# Sheet1.net
KiCad netlist of a schematic drawn in Altium Designer
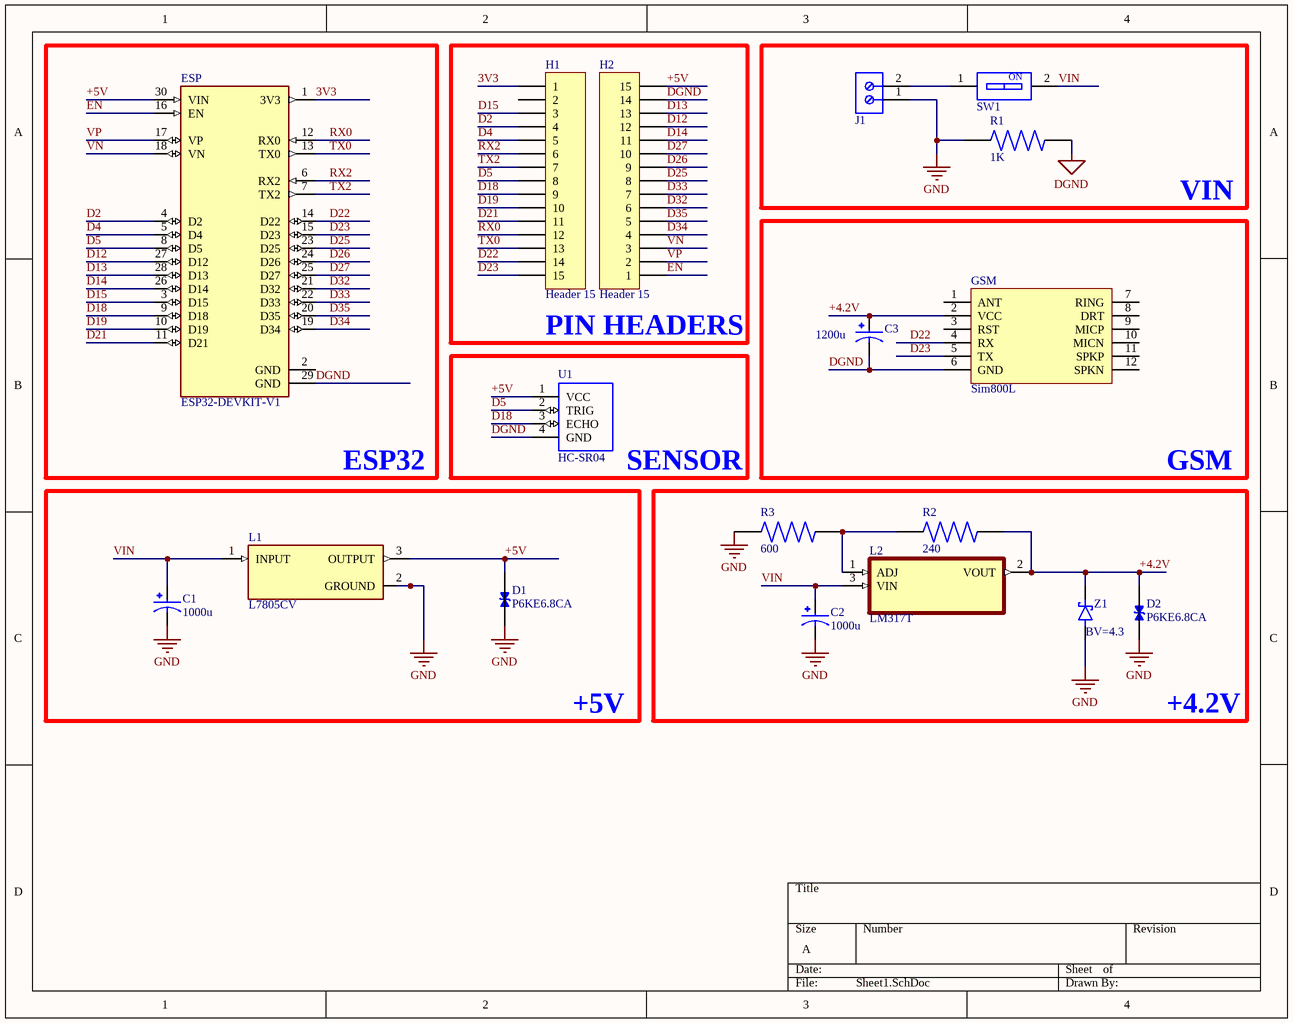
[diagram p0: Sheet1.SchDoc]

(export (version "E")
  (design (tool "Eeschema 10.0.6"))
  (components
    (comp (ref "C1")
      (value "1000u")
      (footprint "CAPPRD500W60D1000H2000")
      (description "1000F 25V Aluminum Electrolytic Capacitors Radial, Can 10000 Hrs @ 105C")
      (fields (field (name "MP") "EEU-FR1E102") (field (name "MF") "Panasonic"))
      (libsource (lib "EEUFR1E102") (part "EEUFR1E102"))
    )
    (comp (ref "C2")
      (value "1000u")
      (footprint "CAPPRD500W60D1000H2000")
      (description "1000F 25V Aluminum Electrolytic Capacitors Radial, Can 10000 Hrs @ 105C")
      (fields (field (name "MP") "EEU-FR1E102") (field (name "MF") "Panasonic"))
      (libsource (lib "EEUFR1E102") (part "EEUFR1E102"))
    )
    (comp (ref "C3")
      (value "1200u")
      (footprint "CAPPRD500W60D1000H2000")
      (description "1000F 25V Aluminum Electrolytic Capacitors Radial, Can 10000 Hrs @ 105C")
      (fields (field (name "MP") "EEU-FR1E102") (field (name "MF") "Panasonic"))
      (libsource (lib "EEUFR1E102") (part "EEUFR1E102"))
    )
    (comp (ref "D1")
      (value "P6KE6.8CA")
      (footprint "DIOAD1300W80L670D310")
      (description "600W, 6.8V, 5%, Bidirectional, TVS")
      (fields (field (name "MF") "Taiwan Semiconductor"))
      (libsource (lib "P6KE6.8CA") (part "P6KE6.8CA"))
    )
    (comp (ref "D2")
      (value "P6KE6.8CA")
      (footprint "DIOAD1300W80L670D310")
      (description "600W, 6.8V, 5%, Bidirectional, TVS")
      (fields (field (name "MF") "Taiwan Semiconductor"))
      (libsource (lib "P6KE6.8CA") (part "P6KE6.8CA"))
    )
    (comp (ref "ESP")
      (value "ESP32-DEVKIT-V1")
      (footprint "MODULE_ESP32_DEVKIT_V1")
      (fields (field (name "MF") "Do it"))
      (libsource (lib "ESP32-DEVKIT-V1") (part "ESP32-DEVKIT-V1"))
    )
    (comp (ref "GSM")
      (value "Sim800L")
      (footprint "Sim800L")
      (libsource (lib "Sim800L_Module") (part "Sim800L"))
    )
    (comp (ref "H1")
      (value "Header 15")
      (footprint "HDR1X15")
      (description "Header, 15-Pin")
      (fields (field (name "PUBLISHER") "Altium Limited"))
      (libsource (lib "Miscellaneous+Connectors") (part "Header 15"))
    )
    (comp (ref "H2")
      (value "Header 15")
      (footprint "HDR1X15")
      (description "Header, 15-Pin")
      (fields (field (name "PUBLISHER") "Altium Limited"))
      (libsource (lib "") (part "Header 15_1"))
    )
    (comp (ref "J1")
      (value "691101710002")
      (footprint "691101710002")
      (description "WR-TBL Series 101 Horizontal Entry Modular, THT, pitch 5mm, 2p")
      (fields (field (name "MANUFACTURER") "Wurth Elektronik"))
      (libsource (lib "Altium_WR-TBL+(rev23f)") (part "691101710002"))
    )
    (comp (ref "L1")
      (value "L7805CV")
      (footprint "TO255P1040X460X1968-3")
      (description "Linear Voltage Regulator IC Positive Fixed 1 Output 1.5A TO-220")
      (fields (field (name "MF") "STMicroelectronics"))
      (libsource (lib "L7805CV") (part "L7805CV"))
    )
    (comp (ref "L2")
      (value "LM317T")
      (footprint "TO254P1054X470X1955-3")
      (description "Linear Voltage Regulator IC Positive Adjustable 1 Output 1.5A TO-220AB")
      (fields (field (name "MF") "onsemi"))
      (libsource (lib "LM317T") (part "LM317T"))
    )
    (comp (ref "R1")
      (value "1K")
      (footprint "RESAD700W45L350D185")
      (description "1 MOhms Â±5% 0.25W, 1/4W Through Hole Resistor Axial - Carbon Film")
      (fields (field (name "MF") "TE Connectivity") (field (name "MP") "3-1623927-1"))
      (libsource (lib "3-1623927-1") (part "3-1623927-1"))
    )
    (comp (ref "R2")
      (value "240")
      (footprint "RESAD700W45L350D185")
      (description "1 MOhms Â±5% 0.25W, 1/4W Through Hole Resistor Axial - Carbon Film")
      (fields (field (name "MF") "TE Connectivity") (field (name "MP") "3-1623927-1"))
      (libsource (lib "3-1623927-1") (part "3-1623927-1"))
    )
    (comp (ref "R3")
      (value "600")
      (footprint "RESAD700W45L350D185")
      (description "1 MOhms Â±5% 0.25W, 1/4W Through Hole Resistor Axial - Carbon Film")
      (fields (field (name "MF") "TE Connectivity") (field (name "MP") "3-1623927-1"))
      (libsource (lib "3-1623927-1") (part "3-1623927-1"))
    )
    (comp (ref "SW1")
      (value "418117170901")
      (footprint "418117170901")
      (description "WS-DITV Compact THT Dip Switch, Flat Actuator, pitch 2.54mm, 1p")
      (fields (field (name "MANUFACTURER") "Wurth Elektronik"))
      (libsource (lib "Altium_WS-DITV+(rev22a)") (part "418117170901"))
    )
    (comp (ref "U1")
      (value "HC-SR04")
      (footprint "XCVR_HC-SR04")
      (description "Ultrasonic Sensor Module")
      (libsource (lib "HC-SR04") (part "HC-SR04"))
    )
    (comp (ref "Z1")
      (value "BV=4.3")
      (footprint "DIOAD1036W78L463D272")
      (description "Zener Diode 12 V 1 W Â±5% Through Hole DO-41")
      (fields (field (name "MF") "ON") (field (name "MP") "1N4742A"))
      (libsource (lib "1N4742A") (part "1N4742A"))
    )
  )
  (nets
    (net (code "1") (name "/+4.2V") (class "Default")
      (node (ref "C3") (pin "P") (pinfunction "P_P") (pintype "passive"))
      (node (ref "D2") (pin "2") (pinfunction "2_2") (pintype "passive"))
      (node (ref "GSM") (pin "2") (pinfunction "VCC_2") (pintype "passive"))
      (node (ref "L2") (pin "2") (pinfunction "VOUT_2") (pintype "output"))
      (node (ref "R2") (pin "2") (pinfunction "2_2") (pintype "passive"))
      (node (ref "Z1") (pin "1") (pinfunction "K_1") (pintype "passive"))
    )
    (net (code "2") (name "/+5V") (class "Default")
      (node (ref "D1") (pin "2") (pinfunction "2_2") (pintype "passive"))
      (node (ref "ESP") (pin "30") (pinfunction "VIN_30") (pintype "input"))
      (node (ref "H2") (pin "15") (pinfunction "15_15") (pintype "passive"))
      (node (ref "L1") (pin "3") (pinfunction "OUTPUT_3") (pintype "output"))
      (node (ref "U1") (pin "1") (pinfunction "VCC_1") (pintype "power_in"))
    )
    (net (code "3") (name "/3V3") (class "Default")
      (node (ref "ESP") (pin "1") (pinfunction "3V3_1") (pintype "output"))
      (node (ref "H1") (pin "1") (pinfunction "1_1") (pintype "passive"))
    )
    (net (code "4") (name "/D2") (class "Default")
      (node (ref "ESP") (pin "4") (pinfunction "D2_4") (pintype "bidirectional"))
      (node (ref "H1") (pin "4") (pinfunction "4_4") (pintype "passive"))
    )
    (net (code "5") (name "/D4") (class "Default")
      (node (ref "ESP") (pin "5") (pinfunction "D4_5") (pintype "bidirectional"))
      (node (ref "H1") (pin "5") (pinfunction "5_5") (pintype "passive"))
    )
    (net (code "6") (name "/D5") (class "Default")
      (node (ref "ESP") (pin "8") (pinfunction "D5_8") (pintype "bidirectional"))
      (node (ref "H1") (pin "8") (pinfunction "8_8") (pintype "passive"))
      (node (ref "U1") (pin "2") (pinfunction "TRIG_2") (pintype "bidirectional"))
    )
    (net (code "7") (name "/D12") (class "Default")
      (node (ref "ESP") (pin "27") (pinfunction "D12_27") (pintype "bidirectional"))
      (node (ref "H2") (pin "12") (pinfunction "12_12") (pintype "passive"))
    )
    (net (code "8") (name "/D13") (class "Default")
      (node (ref "ESP") (pin "28") (pinfunction "D13_28") (pintype "bidirectional"))
      (node (ref "H2") (pin "13") (pinfunction "13_13") (pintype "passive"))
    )
    (net (code "9") (name "/D14") (class "Default")
      (node (ref "ESP") (pin "26") (pinfunction "D14_26") (pintype "bidirectional"))
      (node (ref "H2") (pin "11") (pinfunction "11_11") (pintype "passive"))
    )
    (net (code "10") (name "/D15") (class "Default")
      (node (ref "ESP") (pin "3") (pinfunction "D15_3") (pintype "bidirectional"))
      (node (ref "H1") (pin "3") (pinfunction "3_3") (pintype "passive"))
    )
    (net (code "11") (name "/D18") (class "Default")
      (node (ref "ESP") (pin "9") (pinfunction "D18_9") (pintype "bidirectional"))
      (node (ref "H1") (pin "9") (pinfunction "9_9") (pintype "passive"))
      (node (ref "U1") (pin "3") (pinfunction "ECHO_3") (pintype "bidirectional"))
    )
    (net (code "12") (name "/D19") (class "Default")
      (node (ref "ESP") (pin "10") (pinfunction "D19_10") (pintype "bidirectional"))
      (node (ref "H1") (pin "10") (pinfunction "10_10") (pintype "passive"))
    )
    (net (code "13") (name "/D21") (class "Default")
      (node (ref "ESP") (pin "11") (pinfunction "D21_11") (pintype "bidirectional"))
      (node (ref "H1") (pin "11") (pinfunction "11_11") (pintype "passive"))
    )
    (net (code "14") (name "/D22") (class "Default")
      (node (ref "ESP") (pin "14") (pinfunction "D22_14") (pintype "bidirectional"))
      (node (ref "GSM") (pin "4") (pinfunction "RX_4") (pintype "passive"))
      (node (ref "H1") (pin "14") (pinfunction "14_14") (pintype "passive"))
    )
    (net (code "15") (name "/D23") (class "Default")
      (node (ref "ESP") (pin "15") (pinfunction "D23_15") (pintype "bidirectional"))
      (node (ref "GSM") (pin "5") (pinfunction "TX_5") (pintype "passive"))
      (node (ref "H1") (pin "15") (pinfunction "15_15") (pintype "passive"))
    )
    (net (code "16") (name "/D25") (class "Default")
      (node (ref "ESP") (pin "23") (pinfunction "D25_23") (pintype "bidirectional"))
      (node (ref "H2") (pin "8") (pinfunction "8_8") (pintype "passive"))
    )
    (net (code "17") (name "/D26") (class "Default")
      (node (ref "ESP") (pin "24") (pinfunction "D26_24") (pintype "bidirectional"))
      (node (ref "H2") (pin "9") (pinfunction "9_9") (pintype "passive"))
    )
    (net (code "18") (name "/D27") (class "Default")
      (node (ref "ESP") (pin "25") (pinfunction "D27_25") (pintype "bidirectional"))
      (node (ref "H2") (pin "10") (pinfunction "10_10") (pintype "passive"))
    )
    (net (code "19") (name "/D32") (class "Default")
      (node (ref "ESP") (pin "21") (pinfunction "D32_21") (pintype "bidirectional"))
      (node (ref "H2") (pin "6") (pinfunction "6_6") (pintype "passive"))
    )
    (net (code "20") (name "/D33") (class "Default")
      (node (ref "ESP") (pin "22") (pinfunction "D33_22") (pintype "bidirectional"))
      (node (ref "H2") (pin "7") (pinfunction "7_7") (pintype "passive"))
    )
    (net (code "21") (name "/D34") (class "Default")
      (node (ref "ESP") (pin "19") (pinfunction "D34_19") (pintype "bidirectional"))
      (node (ref "H2") (pin "4") (pinfunction "4_4") (pintype "passive"))
    )
    (net (code "22") (name "/D35") (class "Default")
      (node (ref "ESP") (pin "20") (pinfunction "D35_20") (pintype "bidirectional"))
      (node (ref "H2") (pin "5") (pinfunction "5_5") (pintype "passive"))
    )
    (net (code "23") (name "/EN") (class "Default")
      (node (ref "ESP") (pin "16") (pinfunction "EN_16") (pintype "input"))
      (node (ref "H2") (pin "1") (pinfunction "1_1") (pintype "passive"))
    )
    (net (code "24") (name "/RX0") (class "Default")
      (node (ref "ESP") (pin "12") (pinfunction "RX0_12") (pintype "input"))
      (node (ref "H1") (pin "12") (pinfunction "12_12") (pintype "passive"))
    )
    (net (code "25") (name "/RX2") (class "Default")
      (node (ref "ESP") (pin "6") (pinfunction "RX2_6") (pintype "input"))
      (node (ref "H1") (pin "6") (pinfunction "6_6") (pintype "passive"))
    )
    (net (code "26") (name "/TX0") (class "Default")
      (node (ref "ESP") (pin "13") (pinfunction "TX0_13") (pintype "output"))
      (node (ref "H1") (pin "13") (pinfunction "13_13") (pintype "passive"))
    )
    (net (code "27") (name "/TX2") (class "Default")
      (node (ref "ESP") (pin "7") (pinfunction "TX2_7") (pintype "output"))
      (node (ref "H1") (pin "7") (pinfunction "7_7") (pintype "passive"))
    )
    (net (code "28") (name "/VIN") (class "Default")
      (node (ref "C1") (pin "P") (pinfunction "P_P") (pintype "passive"))
      (node (ref "C2") (pin "P") (pinfunction "P_P") (pintype "passive"))
      (node (ref "L1") (pin "1") (pinfunction "INPUT_1") (pintype "input"))
      (node (ref "L2") (pin "3") (pinfunction "VIN_3") (pintype "input"))
      (node (ref "SW1") (pin "2") (pinfunction "2_2") (pintype "passive"))
    )
    (net (code "29") (name "/VN") (class "Default")
      (node (ref "ESP") (pin "18") (pinfunction "VN_18") (pintype "bidirectional"))
      (node (ref "H2") (pin "3") (pinfunction "3_3") (pintype "passive"))
    )
    (net (code "30") (name "/VP") (class "Default")
      (node (ref "ESP") (pin "17") (pinfunction "VP_17") (pintype "bidirectional"))
      (node (ref "H2") (pin "2") (pinfunction "2_2") (pintype "passive"))
    )
    (net (code "31") (name "DGND") (class "Default")
      (node (ref "C3") (pin "N") (pinfunction "N_N") (pintype "passive"))
      (node (ref "ESP") (pin "29") (pinfunction "GND_29") (pintype "power_in"))
      (node (ref "GSM") (pin "6") (pinfunction "GND_6") (pintype "passive"))
      (node (ref "H2") (pin "14") (pinfunction "14_14") (pintype "passive"))
      (node (ref "R1") (pin "2") (pinfunction "2_2") (pintype "passive"))
      (node (ref "U1") (pin "4") (pinfunction "GND_4") (pintype "power_in"))
    )
    (net (code "32") (name "GND") (class "Default")
      (node (ref "C1") (pin "N") (pinfunction "N_N") (pintype "passive"))
      (node (ref "C2") (pin "N") (pinfunction "N_N") (pintype "passive"))
      (node (ref "D1") (pin "1") (pinfunction "1_1") (pintype "passive"))
      (node (ref "D2") (pin "1") (pinfunction "1_1") (pintype "passive"))
      (node (ref "J1") (pin "1") (pinfunction "1_1") (pintype "passive"))
      (node (ref "L1") (pin "2") (pinfunction "GROUND_2") (pintype "power_in"))
      (node (ref "R1") (pin "1") (pinfunction "1_1") (pintype "passive"))
      (node (ref "R3") (pin "1") (pinfunction "1_1") (pintype "passive"))
      (node (ref "Z1") (pin "2") (pinfunction "A_2") (pintype "passive"))
    )
    (net (code "33") (name "Net-(J1-Pad2)") (class "Default")
      (node (ref "J1") (pin "2") (pinfunction "2_2") (pintype "passive"))
      (node (ref "SW1") (pin "1") (pinfunction "1_1") (pintype "passive"))
    )
    (net (code "34") (name "Net-(L2-ADJ)") (class "Default")
      (node (ref "L2") (pin "1") (pinfunction "ADJ_1") (pintype "input"))
      (node (ref "R2") (pin "1") (pinfunction "1_1") (pintype "passive"))
      (node (ref "R3") (pin "2") (pinfunction "2_2") (pintype "passive"))
    )
    (net (code "35") (name "unconnected-(ESP-GND-Pad2)") (class "Default")
      (node (ref "ESP") (pin "2") (pinfunction "GND_2") (pintype "power_in"))
    )
    (net (code "36") (name "unconnected-(GSM-ANT-Pad1)") (class "Default")
      (node (ref "GSM") (pin "1") (pinfunction "ANT_1") (pintype "passive"))
    )
    (net (code "37") (name "unconnected-(GSM-DRT-Pad8)") (class "Default")
      (node (ref "GSM") (pin "8") (pinfunction "DRT_8") (pintype "passive"))
    )
    (net (code "38") (name "unconnected-(GSM-MICN-Pad10)") (class "Default")
      (node (ref "GSM") (pin "10") (pinfunction "MICN_10") (pintype "passive"))
    )
    (net (code "39") (name "unconnected-(GSM-MICP-Pad9)") (class "Default")
      (node (ref "GSM") (pin "9") (pinfunction "MICP_9") (pintype "passive"))
    )
    (net (code "40") (name "unconnected-(GSM-RING-Pad7)") (class "Default")
      (node (ref "GSM") (pin "7") (pinfunction "RING_7") (pintype "passive"))
    )
    (net (code "41") (name "unconnected-(GSM-RST-Pad3)") (class "Default")
      (node (ref "GSM") (pin "3") (pinfunction "RST_3") (pintype "passive"))
    )
    (net (code "42") (name "unconnected-(GSM-SPKN-Pad12)") (class "Default")
      (node (ref "GSM") (pin "12") (pinfunction "SPKN_12") (pintype "passive"))
    )
    (net (code "43") (name "unconnected-(GSM-SPKP-Pad11)") (class "Default")
      (node (ref "GSM") (pin "11") (pinfunction "SPKP_11") (pintype "passive"))
    )
    (net (code "44") (name "unconnected-(H1-Pad2)") (class "Default")
      (node (ref "H1") (pin "2") (pinfunction "2_2") (pintype "passive"))
    )
  )
)
